# epm_control_2.net
KiCad netlist of a schematic drawn in Altium Designer
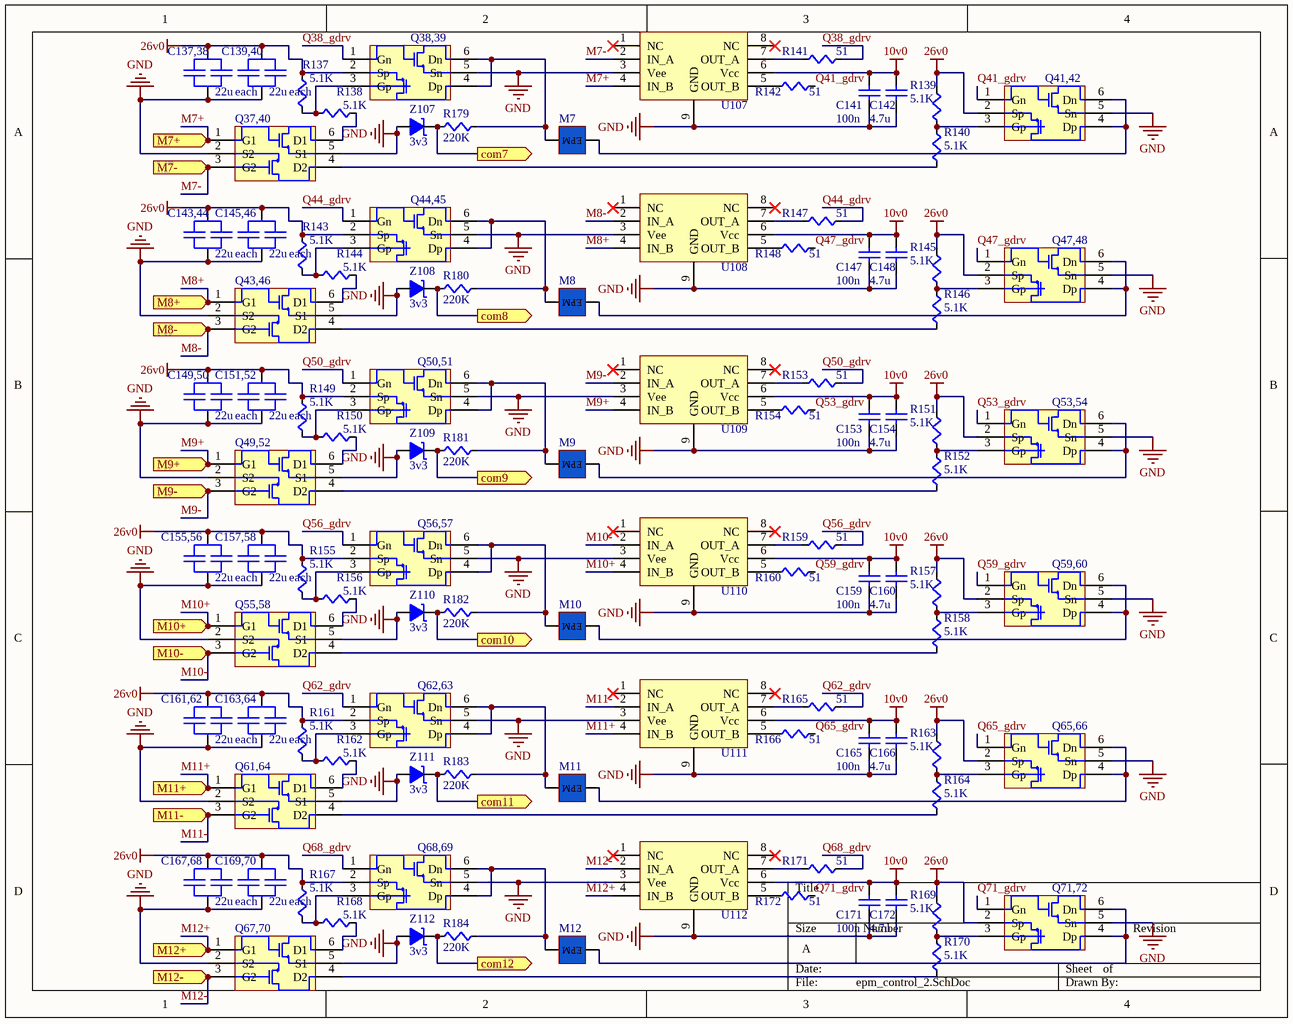
[diagram p0: epm_control_2.SchDoc]

(export (version "E")
  (design (tool "Eeschema 10.0.6"))
  (components
    (comp (ref "C137,38")
      (value "22u")
      (footprint "dicap_smd_1206")
      (fields (field (name "Comment") "Dicap"))
      (libsource (lib "Components") (part "Dicap"))
    )
    (comp (ref "C139,40")
      (value "22u")
      (footprint "dicap_smd_1206")
      (fields (field (name "Comment") "Dicap"))
      (libsource (lib "Components") (part "Dicap"))
    )
    (comp (ref "C141")
      (value "100n")
      (footprint "SMD0603_cap")
      (description "Ceramic Chip Capacitor")
      (fields (field (name "Comment") "Cap"))
      (libsource (lib "Components") (part "Capacitor Ceramic"))
    )
    (comp (ref "C142")
      (value "4.7u")
      (footprint "SMD0603_cap")
      (description "Ceramic Chip Capacitor")
      (fields (field (name "Comment") "Cap"))
      (libsource (lib "Components") (part "Capacitor Ceramic"))
    )
    (comp (ref "C143,44")
      (value "22u")
      (footprint "dicap_smd_1206")
      (fields (field (name "Comment") "Dicap"))
      (libsource (lib "Components") (part "Dicap"))
    )
    (comp (ref "C145,46")
      (value "22u")
      (footprint "dicap_smd_1206")
      (fields (field (name "Comment") "Dicap"))
      (libsource (lib "Components") (part "Dicap"))
    )
    (comp (ref "C147")
      (value "100n")
      (footprint "SMD0603_cap")
      (description "Ceramic Chip Capacitor")
      (fields (field (name "Comment") "Cap"))
      (libsource (lib "Components") (part "Capacitor Ceramic"))
    )
    (comp (ref "C148")
      (value "4.7u")
      (footprint "SMD0603_cap")
      (description "Ceramic Chip Capacitor")
      (fields (field (name "Comment") "Cap"))
      (libsource (lib "Components") (part "Capacitor Ceramic"))
    )
    (comp (ref "C149,50")
      (value "22u")
      (footprint "dicap_smd_1206")
      (fields (field (name "Comment") "Dicap"))
      (libsource (lib "Components") (part "Dicap"))
    )
    (comp (ref "C151,52")
      (value "22u")
      (footprint "dicap_smd_1206")
      (fields (field (name "Comment") "Dicap"))
      (libsource (lib "Components") (part "Dicap"))
    )
    (comp (ref "C153")
      (value "100n")
      (footprint "SMD0603_cap")
      (description "Ceramic Chip Capacitor")
      (fields (field (name "Comment") "Cap"))
      (libsource (lib "Components") (part "Capacitor Ceramic"))
    )
    (comp (ref "C154")
      (value "4.7u")
      (footprint "SMD0603_cap")
      (description "Ceramic Chip Capacitor")
      (fields (field (name "Comment") "Cap"))
      (libsource (lib "Components") (part "Capacitor Ceramic"))
    )
    (comp (ref "C155,56")
      (value "22u")
      (footprint "dicap_smd_1206")
      (fields (field (name "Comment") "Dicap"))
      (libsource (lib "Components") (part "Dicap"))
    )
    (comp (ref "C157,58")
      (value "22u")
      (footprint "dicap_smd_1206")
      (fields (field (name "Comment") "Dicap"))
      (libsource (lib "Components") (part "Dicap"))
    )
    (comp (ref "C159")
      (value "100n")
      (footprint "SMD0603_cap")
      (description "Ceramic Chip Capacitor")
      (fields (field (name "Comment") "Cap"))
      (libsource (lib "Components") (part "Capacitor Ceramic"))
    )
    (comp (ref "C160")
      (value "4.7u")
      (footprint "SMD0603_cap")
      (description "Ceramic Chip Capacitor")
      (fields (field (name "Comment") "Cap"))
      (libsource (lib "Components") (part "Capacitor Ceramic"))
    )
    (comp (ref "C161,62")
      (value "22u")
      (footprint "dicap_smd_1206")
      (fields (field (name "Comment") "Dicap"))
      (libsource (lib "Components") (part "Dicap"))
    )
    (comp (ref "C163,64")
      (value "22u")
      (footprint "dicap_smd_1206")
      (fields (field (name "Comment") "Dicap"))
      (libsource (lib "Components") (part "Dicap"))
    )
    (comp (ref "C165")
      (value "100n")
      (footprint "SMD0603_cap")
      (description "Ceramic Chip Capacitor")
      (fields (field (name "Comment") "Cap"))
      (libsource (lib "Components") (part "Capacitor Ceramic"))
    )
    (comp (ref "C166")
      (value "4.7u")
      (footprint "SMD0603_cap")
      (description "Ceramic Chip Capacitor")
      (fields (field (name "Comment") "Cap"))
      (libsource (lib "Components") (part "Capacitor Ceramic"))
    )
    (comp (ref "C167,68")
      (value "22u")
      (footprint "dicap_smd_1206")
      (fields (field (name "Comment") "Dicap"))
      (libsource (lib "Components") (part "Dicap"))
    )
    (comp (ref "C169,70")
      (value "22u")
      (footprint "dicap_smd_1206")
      (fields (field (name "Comment") "Dicap"))
      (libsource (lib "Components") (part "Dicap"))
    )
    (comp (ref "C171")
      (value "100n")
      (footprint "SMD0603_cap")
      (description "Ceramic Chip Capacitor")
      (fields (field (name "Comment") "Cap"))
      (libsource (lib "Components") (part "Capacitor Ceramic"))
    )
    (comp (ref "C172")
      (value "4.7u")
      (footprint "SMD0603_cap")
      (description "Ceramic Chip Capacitor")
      (fields (field (name "Comment") "Cap"))
      (libsource (lib "Components") (part "Capacitor Ceramic"))
    )
    (comp (ref "M7") (value "EPM") (footprint "40awg_epm") (libsource (lib "Components") (part "EPM")))
    (comp (ref "M8") (value "EPM") (footprint "40awg_epm") (libsource (lib "Components") (part "EPM")))
    (comp (ref "M9") (value "EPM") (footprint "40awg_epm") (libsource (lib "Components") (part "EPM")))
    (comp (ref "M10") (value "EPM") (footprint "40awg_epm") (libsource (lib "Components") (part "EPM")))
    (comp (ref "M11") (value "EPM") (footprint "40awg_epm") (libsource (lib "Components") (part "EPM")))
    (comp (ref "M12") (value "EPM") (footprint "40awg_epm") (libsource (lib "Components") (part "EPM")))
    (comp (ref "Q37,40")
      (value "SI3292")
      (footprint "sot23-6l")
      (libsource (lib "Components") (part "SI3292"))
    )
    (comp (ref "Q38,39")
      (value "DMG6602")
      (footprint "sot23-6l")
      (libsource (lib "Components") (part "DMG6602"))
    )
    (comp (ref "Q41,42")
      (value "DMG6602")
      (footprint "sot23-6l")
      (libsource (lib "Components") (part "DMG6602"))
    )
    (comp (ref "Q43,46")
      (value "SI3292")
      (footprint "sot23-6l")
      (libsource (lib "Components") (part "SI3292"))
    )
    (comp (ref "Q44,45")
      (value "DMG6602")
      (footprint "sot23-6l")
      (libsource (lib "Components") (part "DMG6602"))
    )
    (comp (ref "Q47,48")
      (value "DMG6602")
      (footprint "sot23-6l")
      (libsource (lib "Components") (part "DMG6602"))
    )
    (comp (ref "Q49,52")
      (value "SI3292")
      (footprint "sot23-6l")
      (libsource (lib "Components") (part "SI3292"))
    )
    (comp (ref "Q50,51")
      (value "DMG6602")
      (footprint "sot23-6l")
      (libsource (lib "Components") (part "DMG6602"))
    )
    (comp (ref "Q53,54")
      (value "DMG6602")
      (footprint "sot23-6l")
      (libsource (lib "Components") (part "DMG6602"))
    )
    (comp (ref "Q55,58")
      (value "SI3292")
      (footprint "sot23-6l")
      (libsource (lib "Components") (part "SI3292"))
    )
    (comp (ref "Q56,57")
      (value "DMG6602")
      (footprint "sot23-6l")
      (libsource (lib "Components") (part "DMG6602"))
    )
    (comp (ref "Q59,60")
      (value "DMG6602")
      (footprint "sot23-6l")
      (libsource (lib "Components") (part "DMG6602"))
    )
    (comp (ref "Q61,64")
      (value "SI3292")
      (footprint "sot23-6l")
      (libsource (lib "Components") (part "SI3292"))
    )
    (comp (ref "Q62,63")
      (value "DMG6602")
      (footprint "sot23-6l")
      (libsource (lib "Components") (part "DMG6602"))
    )
    (comp (ref "Q65,66")
      (value "DMG6602")
      (footprint "sot23-6l")
      (libsource (lib "Components") (part "DMG6602"))
    )
    (comp (ref "Q67,70")
      (value "SI3292")
      (footprint "sot23-6l")
      (libsource (lib "Components") (part "SI3292"))
    )
    (comp (ref "Q68,69")
      (value "DMG6602")
      (footprint "sot23-6l")
      (libsource (lib "Components") (part "DMG6602"))
    )
    (comp (ref "Q71,72")
      (value "DMG6602")
      (footprint "sot23-6l")
      (libsource (lib "Components") (part "DMG6602"))
    )
    (comp (ref "R137")
      (value "5.1K")
      (footprint "SMD0603")
      (description "Resistor")
      (fields (field (name "Comment") "Res"))
      (libsource (lib "Components") (part "Resistor"))
    )
    (comp (ref "R138")
      (value "5.1K")
      (footprint "SMD0603")
      (description "Resistor")
      (fields (field (name "Comment") "Res"))
      (libsource (lib "Components") (part "Resistor"))
    )
    (comp (ref "R139")
      (value "5.1K")
      (footprint "SMD0603")
      (description "Resistor")
      (fields (field (name "Comment") "Res"))
      (libsource (lib "Components") (part "Resistor"))
    )
    (comp (ref "R140")
      (value "5.1K")
      (footprint "SMD0603")
      (description "Resistor")
      (fields (field (name "Comment") "Res"))
      (libsource (lib "Components") (part "Resistor"))
    )
    (comp (ref "R141")
      (value "51")
      (footprint "SMD0603")
      (description "Resistor")
      (fields (field (name "Comment") "Res"))
      (libsource (lib "Components") (part "Resistor"))
    )
    (comp (ref "R142")
      (value "51")
      (footprint "SMD0603")
      (description "Resistor")
      (fields (field (name "Comment") "Res"))
      (libsource (lib "Components") (part "Resistor"))
    )
    (comp (ref "R143")
      (value "5.1K")
      (footprint "SMD0603")
      (description "Resistor")
      (fields (field (name "Comment") "Res"))
      (libsource (lib "Components") (part "Resistor"))
    )
    (comp (ref "R144")
      (value "5.1K")
      (footprint "SMD0603")
      (description "Resistor")
      (fields (field (name "Comment") "Res"))
      (libsource (lib "Components") (part "Resistor"))
    )
    (comp (ref "R145")
      (value "5.1K")
      (footprint "SMD0603")
      (description "Resistor")
      (fields (field (name "Comment") "Res"))
      (libsource (lib "Components") (part "Resistor"))
    )
    (comp (ref "R146")
      (value "5.1K")
      (footprint "SMD0603")
      (description "Resistor")
      (fields (field (name "Comment") "Res"))
      (libsource (lib "Components") (part "Resistor"))
    )
    (comp (ref "R147")
      (value "51")
      (footprint "SMD0603")
      (description "Resistor")
      (fields (field (name "Comment") "Res"))
      (libsource (lib "Components") (part "Resistor"))
    )
    (comp (ref "R148")
      (value "51")
      (footprint "SMD0603")
      (description "Resistor")
      (fields (field (name "Comment") "Res"))
      (libsource (lib "Components") (part "Resistor"))
    )
    (comp (ref "R149")
      (value "5.1K")
      (footprint "SMD0603")
      (description "Resistor")
      (fields (field (name "Comment") "Res"))
      (libsource (lib "Components") (part "Resistor"))
    )
    (comp (ref "R150")
      (value "5.1K")
      (footprint "SMD0603")
      (description "Resistor")
      (fields (field (name "Comment") "Res"))
      (libsource (lib "Components") (part "Resistor"))
    )
    (comp (ref "R151")
      (value "5.1K")
      (footprint "SMD0603")
      (description "Resistor")
      (fields (field (name "Comment") "Res"))
      (libsource (lib "Components") (part "Resistor"))
    )
    (comp (ref "R152")
      (value "5.1K")
      (footprint "SMD0603")
      (description "Resistor")
      (fields (field (name "Comment") "Res"))
      (libsource (lib "Components") (part "Resistor"))
    )
    (comp (ref "R153")
      (value "51")
      (footprint "SMD0603")
      (description "Resistor")
      (fields (field (name "Comment") "Res"))
      (libsource (lib "Components") (part "Resistor"))
    )
    (comp (ref "R154")
      (value "51")
      (footprint "SMD0603")
      (description "Resistor")
      (fields (field (name "Comment") "Res"))
      (libsource (lib "Components") (part "Resistor"))
    )
    (comp (ref "R155")
      (value "5.1K")
      (footprint "SMD0603")
      (description "Resistor")
      (fields (field (name "Comment") "Res"))
      (libsource (lib "Components") (part "Resistor"))
    )
    (comp (ref "R156")
      (value "5.1K")
      (footprint "SMD0603")
      (description "Resistor")
      (fields (field (name "Comment") "Res"))
      (libsource (lib "Components") (part "Resistor"))
    )
    (comp (ref "R157")
      (value "5.1K")
      (footprint "SMD0603")
      (description "Resistor")
      (fields (field (name "Comment") "Res"))
      (libsource (lib "Components") (part "Resistor"))
    )
    (comp (ref "R158")
      (value "5.1K")
      (footprint "SMD0603")
      (description "Resistor")
      (fields (field (name "Comment") "Res"))
      (libsource (lib "Components") (part "Resistor"))
    )
    (comp (ref "R159")
      (value "51")
      (footprint "SMD0603")
      (description "Resistor")
      (fields (field (name "Comment") "Res"))
      (libsource (lib "Components") (part "Resistor"))
    )
    (comp (ref "R160")
      (value "51")
      (footprint "SMD0603")
      (description "Resistor")
      (fields (field (name "Comment") "Res"))
      (libsource (lib "Components") (part "Resistor"))
    )
    (comp (ref "R161")
      (value "5.1K")
      (footprint "SMD0603")
      (description "Resistor")
      (fields (field (name "Comment") "Res"))
      (libsource (lib "Components") (part "Resistor"))
    )
    (comp (ref "R162")
      (value "5.1K")
      (footprint "SMD0603")
      (description "Resistor")
      (fields (field (name "Comment") "Res"))
      (libsource (lib "Components") (part "Resistor"))
    )
    (comp (ref "R163")
      (value "5.1K")
      (footprint "SMD0603")
      (description "Resistor")
      (fields (field (name "Comment") "Res"))
      (libsource (lib "Components") (part "Resistor"))
    )
    (comp (ref "R164")
      (value "5.1K")
      (footprint "SMD0603")
      (description "Resistor")
      (fields (field (name "Comment") "Res"))
      (libsource (lib "Components") (part "Resistor"))
    )
    (comp (ref "R165")
      (value "51")
      (footprint "SMD0603")
      (description "Resistor")
      (fields (field (name "Comment") "Res"))
      (libsource (lib "Components") (part "Resistor"))
    )
    (comp (ref "R166")
      (value "51")
      (footprint "SMD0603")
      (description "Resistor")
      (fields (field (name "Comment") "Res"))
      (libsource (lib "Components") (part "Resistor"))
    )
    (comp (ref "R167")
      (value "5.1K")
      (footprint "SMD0603")
      (description "Resistor")
      (fields (field (name "Comment") "Res"))
      (libsource (lib "Components") (part "Resistor"))
    )
    (comp (ref "R168")
      (value "5.1K")
      (footprint "SMD0603")
      (description "Resistor")
      (fields (field (name "Comment") "Res"))
      (libsource (lib "Components") (part "Resistor"))
    )
    (comp (ref "R169")
      (value "5.1K")
      (footprint "SMD0603")
      (description "Resistor")
      (fields (field (name "Comment") "Res"))
      (libsource (lib "Components") (part "Resistor"))
    )
    (comp (ref "R170")
      (value "5.1K")
      (footprint "SMD0603")
      (description "Resistor")
      (fields (field (name "Comment") "Res"))
      (libsource (lib "Components") (part "Resistor"))
    )
    (comp (ref "R171")
      (value "51")
      (footprint "SMD0603")
      (description "Resistor")
      (fields (field (name "Comment") "Res"))
      (libsource (lib "Components") (part "Resistor"))
    )
    (comp (ref "R172")
      (value "51")
      (footprint "SMD0603")
      (description "Resistor")
      (fields (field (name "Comment") "Res"))
      (libsource (lib "Components") (part "Resistor"))
    )
    (comp (ref "R179")
      (value "220K")
      (footprint "SMD0603")
      (description "Resistor")
      (fields (field (name "Comment") "Res"))
      (libsource (lib "Components") (part "Resistor"))
    )
    (comp (ref "R180")
      (value "220K")
      (footprint "SMD0603")
      (description "Resistor")
      (fields (field (name "Comment") "Res"))
      (libsource (lib "Components") (part "Resistor"))
    )
    (comp (ref "R181")
      (value "220K")
      (footprint "SMD0603")
      (description "Resistor")
      (fields (field (name "Comment") "Res"))
      (libsource (lib "Components") (part "Resistor"))
    )
    (comp (ref "R182")
      (value "220K")
      (footprint "SMD0603")
      (description "Resistor")
      (fields (field (name "Comment") "Res"))
      (libsource (lib "Components") (part "Resistor"))
    )
    (comp (ref "R183")
      (value "220K")
      (footprint "SMD0603")
      (description "Resistor")
      (fields (field (name "Comment") "Res"))
      (libsource (lib "Components") (part "Resistor"))
    )
    (comp (ref "R184")
      (value "220K")
      (footprint "SMD0603")
      (description "Resistor")
      (fields (field (name "Comment") "Res"))
      (libsource (lib "Components") (part "Resistor"))
    )
    (comp (ref "U107")
      (value "LM5111-1")
      (footprint "tssop-8")
      (libsource (lib "Components") (part "LM5111-1"))
    )
    (comp (ref "U108")
      (value "LM5111-1")
      (footprint "tssop-8")
      (libsource (lib "Components") (part "LM5111-1"))
    )
    (comp (ref "U109")
      (value "LM5111-1")
      (footprint "tssop-8")
      (libsource (lib "Components") (part "LM5111-1"))
    )
    (comp (ref "U110")
      (value "LM5111-1")
      (footprint "tssop-8")
      (libsource (lib "Components") (part "LM5111-1"))
    )
    (comp (ref "U111")
      (value "LM5111-1")
      (footprint "tssop-8")
      (libsource (lib "Components") (part "LM5111-1"))
    )
    (comp (ref "U112")
      (value "LM5111-1")
      (footprint "tssop-8")
      (libsource (lib "Components") (part "LM5111-1"))
    )
    (comp (ref "Z107")
      (value "3v3")
      (footprint "SOD-323F")
      (fields (field (name "Comment") "Zener"))
      (libsource (lib "Components") (part "Zener"))
    )
    (comp (ref "Z108")
      (value "3v3")
      (footprint "SOD-323F")
      (fields (field (name "Comment") "Zener"))
      (libsource (lib "Components") (part "Zener"))
    )
    (comp (ref "Z109")
      (value "3v3")
      (footprint "SOD-323F")
      (fields (field (name "Comment") "Zener"))
      (libsource (lib "Components") (part "Zener"))
    )
    (comp (ref "Z110")
      (value "3v3")
      (footprint "SOD-323F")
      (fields (field (name "Comment") "Zener"))
      (libsource (lib "Components") (part "Zener"))
    )
    (comp (ref "Z111")
      (value "3v3")
      (footprint "SOD-323F")
      (fields (field (name "Comment") "Zener"))
      (libsource (lib "Components") (part "Zener"))
    )
    (comp (ref "Z112")
      (value "3v3")
      (footprint "SOD-323F")
      (fields (field (name "Comment") "Zener"))
      (libsource (lib "Components") (part "Zener"))
    )
  )
  (nets
    (net (code "1") (name "/M7+") (class "Default")
      (node (ref "Q37,40") (pin "1") (pinfunction "G1_1") (pintype "passive"))
      (node (ref "U107") (pin "4") (pinfunction "IN_B_4") (pintype "passive"))
    )
    (net (code "2") (name "/M7-") (class "Default")
      (node (ref "Q37,40") (pin "3") (pinfunction "G2_3") (pintype "passive"))
      (node (ref "U107") (pin "2") (pinfunction "IN_A_2") (pintype "passive"))
    )
    (net (code "3") (name "/M8+") (class "Default")
      (node (ref "Q43,46") (pin "1") (pinfunction "G1_1") (pintype "passive"))
      (node (ref "U108") (pin "4") (pinfunction "IN_B_4") (pintype "passive"))
    )
    (net (code "4") (name "/M8-") (class "Default")
      (node (ref "Q43,46") (pin "3") (pinfunction "G2_3") (pintype "passive"))
      (node (ref "U108") (pin "2") (pinfunction "IN_A_2") (pintype "passive"))
    )
    (net (code "5") (name "/M9+") (class "Default")
      (node (ref "Q49,52") (pin "1") (pinfunction "G1_1") (pintype "passive"))
      (node (ref "U109") (pin "4") (pinfunction "IN_B_4") (pintype "passive"))
    )
    (net (code "6") (name "/M9-") (class "Default")
      (node (ref "Q49,52") (pin "3") (pinfunction "G2_3") (pintype "passive"))
      (node (ref "U109") (pin "2") (pinfunction "IN_A_2") (pintype "passive"))
    )
    (net (code "7") (name "/M10+") (class "Default")
      (node (ref "Q55,58") (pin "1") (pinfunction "G1_1") (pintype "passive"))
      (node (ref "U110") (pin "4") (pinfunction "IN_B_4") (pintype "passive"))
    )
    (net (code "8") (name "/M10-") (class "Default")
      (node (ref "Q55,58") (pin "3") (pinfunction "G2_3") (pintype "passive"))
      (node (ref "U110") (pin "2") (pinfunction "IN_A_2") (pintype "passive"))
    )
    (net (code "9") (name "/M11+") (class "Default")
      (node (ref "Q61,64") (pin "1") (pinfunction "G1_1") (pintype "passive"))
      (node (ref "U111") (pin "4") (pinfunction "IN_B_4") (pintype "passive"))
    )
    (net (code "10") (name "/M11-") (class "Default")
      (node (ref "Q61,64") (pin "3") (pinfunction "G2_3") (pintype "passive"))
      (node (ref "U111") (pin "2") (pinfunction "IN_A_2") (pintype "passive"))
    )
    (net (code "11") (name "/M12+") (class "Default")
      (node (ref "Q67,70") (pin "1") (pinfunction "G1_1") (pintype "passive"))
      (node (ref "U112") (pin "4") (pinfunction "IN_B_4") (pintype "passive"))
    )
    (net (code "12") (name "/M12-") (class "Default")
      (node (ref "Q67,70") (pin "3") (pinfunction "G2_3") (pintype "passive"))
      (node (ref "U112") (pin "2") (pinfunction "IN_A_2") (pintype "passive"))
    )
    (net (code "13") (name "/Q38_gdrv") (class "Default")
      (node (ref "Q38,39") (pin "1") (pinfunction "Gn_1") (pintype "passive"))
      (node (ref "R141") (pin "1") (pinfunction "1_1") (pintype "passive"))
    )
    (net (code "14") (name "/Q41_gdrv") (class "Default")
      (node (ref "Q41,42") (pin "1") (pinfunction "Gn_1") (pintype "passive"))
      (node (ref "R142") (pin "1") (pinfunction "1_1") (pintype "passive"))
    )
    (net (code "15") (name "/Q44_gdrv") (class "Default")
      (node (ref "Q44,45") (pin "1") (pinfunction "Gn_1") (pintype "passive"))
      (node (ref "R147") (pin "1") (pinfunction "1_1") (pintype "passive"))
    )
    (net (code "16") (name "/Q47_gdrv") (class "Default")
      (node (ref "Q47,48") (pin "1") (pinfunction "Gn_1") (pintype "passive"))
      (node (ref "R148") (pin "1") (pinfunction "1_1") (pintype "passive"))
    )
    (net (code "17") (name "/Q50_gdrv") (class "Default")
      (node (ref "Q50,51") (pin "1") (pinfunction "Gn_1") (pintype "passive"))
      (node (ref "R153") (pin "1") (pinfunction "1_1") (pintype "passive"))
    )
    (net (code "18") (name "/Q53_gdrv") (class "Default")
      (node (ref "Q53,54") (pin "1") (pinfunction "Gn_1") (pintype "passive"))
      (node (ref "R154") (pin "1") (pinfunction "1_1") (pintype "passive"))
    )
    (net (code "19") (name "/Q56_gdrv") (class "Default")
      (node (ref "Q56,57") (pin "1") (pinfunction "Gn_1") (pintype "passive"))
      (node (ref "R159") (pin "1") (pinfunction "1_1") (pintype "passive"))
    )
    (net (code "20") (name "/Q59_gdrv") (class "Default")
      (node (ref "Q59,60") (pin "1") (pinfunction "Gn_1") (pintype "passive"))
      (node (ref "R160") (pin "1") (pinfunction "1_1") (pintype "passive"))
    )
    (net (code "21") (name "/Q62_gdrv") (class "Default")
      (node (ref "Q62,63") (pin "1") (pinfunction "Gn_1") (pintype "passive"))
      (node (ref "R165") (pin "1") (pinfunction "1_1") (pintype "passive"))
    )
    (net (code "22") (name "/Q65_gdrv") (class "Default")
      (node (ref "Q65,66") (pin "1") (pinfunction "Gn_1") (pintype "passive"))
      (node (ref "R166") (pin "1") (pinfunction "1_1") (pintype "passive"))
    )
    (net (code "23") (name "/Q68_gdrv") (class "Default")
      (node (ref "Q68,69") (pin "1") (pinfunction "Gn_1") (pintype "passive"))
      (node (ref "R171") (pin "1") (pinfunction "1_1") (pintype "passive"))
    )
    (net (code "24") (name "/Q71_gdrv") (class "Default")
      (node (ref "Q71,72") (pin "1") (pinfunction "Gn_1") (pintype "passive"))
      (node (ref "R172") (pin "1") (pinfunction "1_1") (pintype "passive"))
    )
    (net (code "25") (name "/com7") (class "Default")
      (node (ref "R179") (pin "1") (pinfunction "1_1") (pintype "passive"))
      (node (ref "Z107") (pin "K") (pinfunction "2_K") (pintype "passive"))
    )
    (net (code "26") (name "/com8") (class "Default")
      (node (ref "R180") (pin "1") (pinfunction "1_1") (pintype "passive"))
      (node (ref "Z108") (pin "K") (pinfunction "2_K") (pintype "passive"))
    )
    (net (code "27") (name "/com9") (class "Default")
      (node (ref "R181") (pin "1") (pinfunction "1_1") (pintype "passive"))
      (node (ref "Z109") (pin "K") (pinfunction "2_K") (pintype "passive"))
    )
    (net (code "28") (name "/com10") (class "Default")
      (node (ref "R182") (pin "1") (pinfunction "1_1") (pintype "passive"))
      (node (ref "Z110") (pin "K") (pinfunction "2_K") (pintype "passive"))
    )
    (net (code "29") (name "/com11") (class "Default")
      (node (ref "R183") (pin "1") (pinfunction "1_1") (pintype "passive"))
      (node (ref "Z111") (pin "K") (pinfunction "2_K") (pintype "passive"))
    )
    (net (code "30") (name "/com12") (class "Default")
      (node (ref "R184") (pin "1") (pinfunction "1_1") (pintype "passive"))
      (node (ref "Z112") (pin "K") (pinfunction "2_K") (pintype "passive"))
    )
    (net (code "31") (name "10v0") (class "Default")
      (node (ref "C141") (pin "2") (pinfunction "2_2") (pintype "passive"))
      (node (ref "C142") (pin "2") (pinfunction "2_2") (pintype "passive"))
      (node (ref "C147") (pin "2") (pinfunction "2_2") (pintype "passive"))
      (node (ref "C148") (pin "2") (pinfunction "2_2") (pintype "passive"))
      (node (ref "C153") (pin "2") (pinfunction "2_2") (pintype "passive"))
      (node (ref "C154") (pin "2") (pinfunction "2_2") (pintype "passive"))
      (node (ref "C159") (pin "2") (pinfunction "2_2") (pintype "passive"))
      (node (ref "C160") (pin "2") (pinfunction "2_2") (pintype "passive"))
      (node (ref "C165") (pin "2") (pinfunction "2_2") (pintype "passive"))
      (node (ref "C166") (pin "2") (pinfunction "2_2") (pintype "passive"))
      (node (ref "C171") (pin "2") (pinfunction "2_2") (pintype "passive"))
      (node (ref "C172") (pin "2") (pinfunction "2_2") (pintype "passive"))
      (node (ref "U107") (pin "6") (pinfunction "Vcc_6") (pintype "passive"))
      (node (ref "U108") (pin "6") (pinfunction "Vcc_6") (pintype "passive"))
      (node (ref "U109") (pin "6") (pinfunction "Vcc_6") (pintype "passive"))
      (node (ref "U110") (pin "6") (pinfunction "Vcc_6") (pintype "passive"))
      (node (ref "U111") (pin "6") (pinfunction "Vcc_6") (pintype "passive"))
      (node (ref "U112") (pin "6") (pinfunction "Vcc_6") (pintype "passive"))
    )
    (net (code "32") (name "26v0") (class "Default")
      (node (ref "C137,38") (pin "2") (pinfunction "2_2") (pintype "passive"))
      (node (ref "C139,40") (pin "2") (pinfunction "2_2") (pintype "passive"))
      (node (ref "C143,44") (pin "2") (pinfunction "2_2") (pintype "passive"))
      (node (ref "C145,46") (pin "2") (pinfunction "2_2") (pintype "passive"))
      (node (ref "C149,50") (pin "2") (pinfunction "2_2") (pintype "passive"))
      (node (ref "C151,52") (pin "2") (pinfunction "2_2") (pintype "passive"))
      (node (ref "C155,56") (pin "2") (pinfunction "2_2") (pintype "passive"))
      (node (ref "C157,58") (pin "2") (pinfunction "2_2") (pintype "passive"))
      (node (ref "C161,62") (pin "2") (pinfunction "2_2") (pintype "passive"))
      (node (ref "C163,64") (pin "2") (pinfunction "2_2") (pintype "passive"))
      (node (ref "C167,68") (pin "2") (pinfunction "2_2") (pintype "passive"))
      (node (ref "C169,70") (pin "2") (pinfunction "2_2") (pintype "passive"))
      (node (ref "Q38,39") (pin "2") (pinfunction "Sp_2") (pintype "passive"))
      (node (ref "Q41,42") (pin "2") (pinfunction "Sp_2") (pintype "passive"))
      (node (ref "Q44,45") (pin "2") (pinfunction "Sp_2") (pintype "passive"))
      (node (ref "Q47,48") (pin "2") (pinfunction "Sp_2") (pintype "passive"))
      (node (ref "Q50,51") (pin "2") (pinfunction "Sp_2") (pintype "passive"))
      (node (ref "Q53,54") (pin "2") (pinfunction "Sp_2") (pintype "passive"))
      (node (ref "Q56,57") (pin "2") (pinfunction "Sp_2") (pintype "passive"))
      (node (ref "Q59,60") (pin "2") (pinfunction "Sp_2") (pintype "passive"))
      (node (ref "Q62,63") (pin "2") (pinfunction "Sp_2") (pintype "passive"))
      (node (ref "Q65,66") (pin "2") (pinfunction "Sp_2") (pintype "passive"))
      (node (ref "Q68,69") (pin "2") (pinfunction "Sp_2") (pintype "passive"))
      (node (ref "Q71,72") (pin "2") (pinfunction "Sp_2") (pintype "passive"))
      (node (ref "R137") (pin "2") (pinfunction "2_2") (pintype "passive"))
      (node (ref "R139") (pin "2") (pinfunction "2_2") (pintype "passive"))
      (node (ref "R143") (pin "2") (pinfunction "2_2") (pintype "passive"))
      (node (ref "R145") (pin "2") (pinfunction "2_2") (pintype "passive"))
      (node (ref "R149") (pin "2") (pinfunction "2_2") (pintype "passive"))
      (node (ref "R151") (pin "2") (pinfunction "2_2") (pintype "passive"))
      (node (ref "R155") (pin "2") (pinfunction "2_2") (pintype "passive"))
      (node (ref "R157") (pin "2") (pinfunction "2_2") (pintype "passive"))
      (node (ref "R161") (pin "2") (pinfunction "2_2") (pintype "passive"))
      (node (ref "R163") (pin "2") (pinfunction "2_2") (pintype "passive"))
      (node (ref "R167") (pin "2") (pinfunction "2_2") (pintype "passive"))
      (node (ref "R169") (pin "2") (pinfunction "2_2") (pintype "passive"))
    )
    (net (code "33") (name "GND") (class "Default")
      (node (ref "C137,38") (pin "1") (pinfunction "1_1") (pintype "passive"))
      (node (ref "C139,40") (pin "1") (pinfunction "1_1") (pintype "passive"))
      (node (ref "C141") (pin "1") (pinfunction "1_1") (pintype "passive"))
      (node (ref "C142") (pin "1") (pinfunction "1_1") (pintype "passive"))
      (node (ref "C143,44") (pin "1") (pinfunction "1_1") (pintype "passive"))
      (node (ref "C145,46") (pin "1") (pinfunction "1_1") (pintype "passive"))
      (node (ref "C147") (pin "1") (pinfunction "1_1") (pintype "passive"))
      (node (ref "C148") (pin "1") (pinfunction "1_1") (pintype "passive"))
      (node (ref "C149,50") (pin "1") (pinfunction "1_1") (pintype "passive"))
      (node (ref "C151,52") (pin "1") (pinfunction "1_1") (pintype "passive"))
      (node (ref "C153") (pin "1") (pinfunction "1_1") (pintype "passive"))
      (node (ref "C154") (pin "1") (pinfunction "1_1") (pintype "passive"))
      (node (ref "C155,56") (pin "1") (pinfunction "1_1") (pintype "passive"))
      (node (ref "C157,58") (pin "1") (pinfunction "1_1") (pintype "passive"))
      (node (ref "C159") (pin "1") (pinfunction "1_1") (pintype "passive"))
      (node (ref "C160") (pin "1") (pinfunction "1_1") (pintype "passive"))
      (node (ref "C161,62") (pin "1") (pinfunction "1_1") (pintype "passive"))
      (node (ref "C163,64") (pin "1") (pinfunction "1_1") (pintype "passive"))
      (node (ref "C165") (pin "1") (pinfunction "1_1") (pintype "passive"))
      (node (ref "C166") (pin "1") (pinfunction "1_1") (pintype "passive"))
      (node (ref "C167,68") (pin "1") (pinfunction "1_1") (pintype "passive"))
      (node (ref "C169,70") (pin "1") (pinfunction "1_1") (pintype "passive"))
      (node (ref "C171") (pin "1") (pinfunction "1_1") (pintype "passive"))
      (node (ref "C172") (pin "1") (pinfunction "1_1") (pintype "passive"))
      (node (ref "Q37,40") (pin "2") (pinfunction "S2_2") (pintype "passive"))
      (node (ref "Q37,40") (pin "5") (pinfunction "S1_5") (pintype "passive"))
      (node (ref "Q38,39") (pin "5") (pinfunction "Sn_5") (pintype "passive"))
      (node (ref "Q41,42") (pin "5") (pinfunction "Sn_5") (pintype "passive"))
      (node (ref "Q43,46") (pin "2") (pinfunction "S2_2") (pintype "passive"))
      (node (ref "Q43,46") (pin "5") (pinfunction "S1_5") (pintype "passive"))
      (node (ref "Q44,45") (pin "5") (pinfunction "Sn_5") (pintype "passive"))
      (node (ref "Q47,48") (pin "5") (pinfunction "Sn_5") (pintype "passive"))
      (node (ref "Q49,52") (pin "2") (pinfunction "S2_2") (pintype "passive"))
      (node (ref "Q49,52") (pin "5") (pinfunction "S1_5") (pintype "passive"))
      (node (ref "Q50,51") (pin "5") (pinfunction "Sn_5") (pintype "passive"))
      (node (ref "Q53,54") (pin "5") (pinfunction "Sn_5") (pintype "passive"))
      (node (ref "Q55,58") (pin "2") (pinfunction "S2_2") (pintype "passive"))
      (node (ref "Q55,58") (pin "5") (pinfunction "S1_5") (pintype "passive"))
      (node (ref "Q56,57") (pin "5") (pinfunction "Sn_5") (pintype "passive"))
      (node (ref "Q59,60") (pin "5") (pinfunction "Sn_5") (pintype "passive"))
      (node (ref "Q61,64") (pin "2") (pinfunction "S2_2") (pintype "passive"))
      (node (ref "Q61,64") (pin "5") (pinfunction "S1_5") (pintype "passive"))
      (node (ref "Q62,63") (pin "5") (pinfunction "Sn_5") (pintype "passive"))
      (node (ref "Q65,66") (pin "5") (pinfunction "Sn_5") (pintype "passive"))
      (node (ref "Q67,70") (pin "2") (pinfunction "S2_2") (pintype "passive"))
      (node (ref "Q67,70") (pin "5") (pinfunction "S1_5") (pintype "passive"))
      (node (ref "Q68,69") (pin "5") (pinfunction "Sn_5") (pintype "passive"))
      (node (ref "Q71,72") (pin "5") (pinfunction "Sn_5") (pintype "passive"))
      (node (ref "U107") (pin "3") (pinfunction "Vee_3") (pintype "passive"))
      (node (ref "U107") (pin "9") (pinfunction "GND_9") (pintype "passive"))
      (node (ref "U108") (pin "3") (pinfunction "Vee_3") (pintype "passive"))
      (node (ref "U108") (pin "9") (pinfunction "GND_9") (pintype "passive"))
      (node (ref "U109") (pin "3") (pinfunction "Vee_3") (pintype "passive"))
      (node (ref "U109") (pin "9") (pinfunction "GND_9") (pintype "passive"))
      (node (ref "U110") (pin "3") (pinfunction "Vee_3") (pintype "passive"))
      (node (ref "U110") (pin "9") (pinfunction "GND_9") (pintype "passive"))
      (node (ref "U111") (pin "3") (pinfunction "Vee_3") (pintype "passive"))
      (node (ref "U111") (pin "9") (pinfunction "GND_9") (pintype "passive"))
      (node (ref "U112") (pin "3") (pinfunction "Vee_3") (pintype "passive"))
      (node (ref "U112") (pin "9") (pinfunction "GND_9") (pintype "passive"))
      (node (ref "Z107") (pin "A") (pintype "passive"))
      (node (ref "Z108") (pin "A") (pintype "passive"))
      (node (ref "Z109") (pin "A") (pintype "passive"))
      (node (ref "Z110") (pin "A") (pintype "passive"))
      (node (ref "Z111") (pin "A") (pintype "passive"))
      (node (ref "Z112") (pin "A") (pintype "passive"))
    )
    (net (code "34") (name "Net-(Q37,40-D1)") (class "Default")
      (node (ref "Q37,40") (pin "6") (pinfunction "D1_6") (pintype "passive"))
      (node (ref "R138") (pin "1") (pinfunction "1_1") (pintype "passive"))
    )
    (net (code "35") (name "Net-(Q37,40-D2)") (class "Default")
      (node (ref "Q37,40") (pin "4") (pinfunction "D2_4") (pintype "passive"))
      (node (ref "R140") (pin "1") (pinfunction "1_1") (pintype "passive"))
    )
    (net (code "36") (name "Net-(Q38,39-Dn)") (class "Default")
      (node (ref "M7") (pin "2") (pinfunction "2_2") (pintype "passive"))
      (node (ref "Q38,39") (pin "4") (pinfunction "Dp_4") (pintype "passive"))
      (node (ref "Q38,39") (pin "6") (pinfunction "Dn_6") (pintype "passive"))
      (node (ref "R179") (pin "2") (pinfunction "2_2") (pintype "passive"))
    )
    (net (code "37") (name "Net-(Q38,39-Gp)") (class "Default")
      (node (ref "Q38,39") (pin "3") (pinfunction "Gp_3") (pintype "passive"))
      (node (ref "R137") (pin "1") (pinfunction "1_1") (pintype "passive"))
      (node (ref "R138") (pin "2") (pinfunction "2_2") (pintype "passive"))
    )
    (net (code "38") (name "Net-(Q41,42-Dn)") (class "Default")
      (node (ref "M7") (pin "1") (pinfunction "1_1") (pintype "passive"))
      (node (ref "Q41,42") (pin "4") (pinfunction "Dp_4") (pintype "passive"))
      (node (ref "Q41,42") (pin "6") (pinfunction "Dn_6") (pintype "passive"))
    )
    (net (code "39") (name "Net-(Q41,42-Gp)") (class "Default")
      (node (ref "Q41,42") (pin "3") (pinfunction "Gp_3") (pintype "passive"))
      (node (ref "R139") (pin "1") (pinfunction "1_1") (pintype "passive"))
      (node (ref "R140") (pin "2") (pinfunction "2_2") (pintype "passive"))
    )
    (net (code "40") (name "Net-(Q43,46-D1)") (class "Default")
      (node (ref "Q43,46") (pin "6") (pinfunction "D1_6") (pintype "passive"))
      (node (ref "R144") (pin "1") (pinfunction "1_1") (pintype "passive"))
    )
    (net (code "41") (name "Net-(Q43,46-D2)") (class "Default")
      (node (ref "Q43,46") (pin "4") (pinfunction "D2_4") (pintype "passive"))
      (node (ref "R146") (pin "1") (pinfunction "1_1") (pintype "passive"))
    )
    (net (code "42") (name "Net-(Q44,45-Dn)") (class "Default")
      (node (ref "M8") (pin "2") (pinfunction "2_2") (pintype "passive"))
      (node (ref "Q44,45") (pin "4") (pinfunction "Dp_4") (pintype "passive"))
      (node (ref "Q44,45") (pin "6") (pinfunction "Dn_6") (pintype "passive"))
      (node (ref "R180") (pin "2") (pinfunction "2_2") (pintype "passive"))
    )
    (net (code "43") (name "Net-(Q44,45-Gp)") (class "Default")
      (node (ref "Q44,45") (pin "3") (pinfunction "Gp_3") (pintype "passive"))
      (node (ref "R143") (pin "1") (pinfunction "1_1") (pintype "passive"))
      (node (ref "R144") (pin "2") (pinfunction "2_2") (pintype "passive"))
    )
    (net (code "44") (name "Net-(Q47,48-Dn)") (class "Default")
      (node (ref "M8") (pin "1") (pinfunction "1_1") (pintype "passive"))
      (node (ref "Q47,48") (pin "4") (pinfunction "Dp_4") (pintype "passive"))
      (node (ref "Q47,48") (pin "6") (pinfunction "Dn_6") (pintype "passive"))
    )
    (net (code "45") (name "Net-(Q47,48-Gp)") (class "Default")
      (node (ref "Q47,48") (pin "3") (pinfunction "Gp_3") (pintype "passive"))
      (node (ref "R145") (pin "1") (pinfunction "1_1") (pintype "passive"))
      (node (ref "R146") (pin "2") (pinfunction "2_2") (pintype "passive"))
    )
    (net (code "46") (name "Net-(Q49,52-D1)") (class "Default")
      (node (ref "Q49,52") (pin "6") (pinfunction "D1_6") (pintype "passive"))
      (node (ref "R150") (pin "1") (pinfunction "1_1") (pintype "passive"))
    )
    (net (code "47") (name "Net-(Q49,52-D2)") (class "Default")
      (node (ref "Q49,52") (pin "4") (pinfunction "D2_4") (pintype "passive"))
      (node (ref "R152") (pin "1") (pinfunction "1_1") (pintype "passive"))
    )
    (net (code "48") (name "Net-(Q50,51-Dn)") (class "Default")
      (node (ref "M9") (pin "2") (pinfunction "2_2") (pintype "passive"))
      (node (ref "Q50,51") (pin "4") (pinfunction "Dp_4") (pintype "passive"))
      (node (ref "Q50,51") (pin "6") (pinfunction "Dn_6") (pintype "passive"))
      (node (ref "R181") (pin "2") (pinfunction "2_2") (pintype "passive"))
    )
    (net (code "49") (name "Net-(Q50,51-Gp)") (class "Default")
      (node (ref "Q50,51") (pin "3") (pinfunction "Gp_3") (pintype "passive"))
      (node (ref "R149") (pin "1") (pinfunction "1_1") (pintype "passive"))
      (node (ref "R150") (pin "2") (pinfunction "2_2") (pintype "passive"))
    )
    (net (code "50") (name "Net-(Q53,54-Dn)") (class "Default")
      (node (ref "M9") (pin "1") (pinfunction "1_1") (pintype "passive"))
      (node (ref "Q53,54") (pin "4") (pinfunction "Dp_4") (pintype "passive"))
      (node (ref "Q53,54") (pin "6") (pinfunction "Dn_6") (pintype "passive"))
    )
    (net (code "51") (name "Net-(Q53,54-Gp)") (class "Default")
      (node (ref "Q53,54") (pin "3") (pinfunction "Gp_3") (pintype "passive"))
      (node (ref "R151") (pin "1") (pinfunction "1_1") (pintype "passive"))
      (node (ref "R152") (pin "2") (pinfunction "2_2") (pintype "passive"))
    )
    (net (code "52") (name "Net-(Q55,58-D1)") (class "Default")
      (node (ref "Q55,58") (pin "6") (pinfunction "D1_6") (pintype "passive"))
      (node (ref "R156") (pin "1") (pinfunction "1_1") (pintype "passive"))
    )
    (net (code "53") (name "Net-(Q55,58-D2)") (class "Default")
      (node (ref "Q55,58") (pin "4") (pinfunction "D2_4") (pintype "passive"))
      (node (ref "R158") (pin "1") (pinfunction "1_1") (pintype "passive"))
    )
    (net (code "54") (name "Net-(Q56,57-Dn)") (class "Default")
      (node (ref "M10") (pin "2") (pinfunction "2_2") (pintype "passive"))
      (node (ref "Q56,57") (pin "4") (pinfunction "Dp_4") (pintype "passive"))
      (node (ref "Q56,57") (pin "6") (pinfunction "Dn_6") (pintype "passive"))
      (node (ref "R182") (pin "2") (pinfunction "2_2") (pintype "passive"))
    )
    (net (code "55") (name "Net-(Q56,57-Gp)") (class "Default")
      (node (ref "Q56,57") (pin "3") (pinfunction "Gp_3") (pintype "passive"))
      (node (ref "R155") (pin "1") (pinfunction "1_1") (pintype "passive"))
      (node (ref "R156") (pin "2") (pinfunction "2_2") (pintype "passive"))
    )
    (net (code "56") (name "Net-(Q59,60-Dn)") (class "Default")
      (node (ref "M10") (pin "1") (pinfunction "1_1") (pintype "passive"))
      (node (ref "Q59,60") (pin "4") (pinfunction "Dp_4") (pintype "passive"))
      (node (ref "Q59,60") (pin "6") (pinfunction "Dn_6") (pintype "passive"))
    )
    (net (code "57") (name "Net-(Q59,60-Gp)") (class "Default")
      (node (ref "Q59,60") (pin "3") (pinfunction "Gp_3") (pintype "passive"))
      (node (ref "R157") (pin "1") (pinfunction "1_1") (pintype "passive"))
      (node (ref "R158") (pin "2") (pinfunction "2_2") (pintype "passive"))
    )
    (net (code "58") (name "Net-(Q61,64-D1)") (class "Default")
      (node (ref "Q61,64") (pin "6") (pinfunction "D1_6") (pintype "passive"))
      (node (ref "R162") (pin "1") (pinfunction "1_1") (pintype "passive"))
    )
    (net (code "59") (name "Net-(Q61,64-D2)") (class "Default")
      (node (ref "Q61,64") (pin "4") (pinfunction "D2_4") (pintype "passive"))
      (node (ref "R164") (pin "1") (pinfunction "1_1") (pintype "passive"))
    )
    (net (code "60") (name "Net-(Q62,63-Dn)") (class "Default")
      (node (ref "M11") (pin "2") (pinfunction "2_2") (pintype "passive"))
      (node (ref "Q62,63") (pin "4") (pinfunction "Dp_4") (pintype "passive"))
      (node (ref "Q62,63") (pin "6") (pinfunction "Dn_6") (pintype "passive"))
      (node (ref "R183") (pin "2") (pinfunction "2_2") (pintype "passive"))
    )
    (net (code "61") (name "Net-(Q62,63-Gp)") (class "Default")
      (node (ref "Q62,63") (pin "3") (pinfunction "Gp_3") (pintype "passive"))
      (node (ref "R161") (pin "1") (pinfunction "1_1") (pintype "passive"))
      (node (ref "R162") (pin "2") (pinfunction "2_2") (pintype "passive"))
    )
    (net (code "62") (name "Net-(Q65,66-Dn)") (class "Default")
      (node (ref "M11") (pin "1") (pinfunction "1_1") (pintype "passive"))
      (node (ref "Q65,66") (pin "4") (pinfunction "Dp_4") (pintype "passive"))
      (node (ref "Q65,66") (pin "6") (pinfunction "Dn_6") (pintype "passive"))
    )
    (net (code "63") (name "Net-(Q65,66-Gp)") (class "Default")
      (node (ref "Q65,66") (pin "3") (pinfunction "Gp_3") (pintype "passive"))
      (node (ref "R163") (pin "1") (pinfunction "1_1") (pintype "passive"))
      (node (ref "R164") (pin "2") (pinfunction "2_2") (pintype "passive"))
    )
    (net (code "64") (name "Net-(Q67,70-D1)") (class "Default")
      (node (ref "Q67,70") (pin "6") (pinfunction "D1_6") (pintype "passive"))
      (node (ref "R168") (pin "1") (pinfunction "1_1") (pintype "passive"))
    )
    (net (code "65") (name "Net-(Q67,70-D2)") (class "Default")
      (node (ref "Q67,70") (pin "4") (pinfunction "D2_4") (pintype "passive"))
      (node (ref "R170") (pin "1") (pinfunction "1_1") (pintype "passive"))
    )
    (net (code "66") (name "Net-(Q68,69-Dn)") (class "Default")
      (node (ref "M12") (pin "2") (pinfunction "2_2") (pintype "passive"))
      (node (ref "Q68,69") (pin "4") (pinfunction "Dp_4") (pintype "passive"))
      (node (ref "Q68,69") (pin "6") (pinfunction "Dn_6") (pintype "passive"))
      (node (ref "R184") (pin "2") (pinfunction "2_2") (pintype "passive"))
    )
    (net (code "67") (name "Net-(Q68,69-Gp)") (class "Default")
      (node (ref "Q68,69") (pin "3") (pinfunction "Gp_3") (pintype "passive"))
      (node (ref "R167") (pin "1") (pinfunction "1_1") (pintype "passive"))
      (node (ref "R168") (pin "2") (pinfunction "2_2") (pintype "passive"))
    )
    (net (code "68") (name "Net-(Q71,72-Dn)") (class "Default")
      (node (ref "M12") (pin "1") (pinfunction "1_1") (pintype "passive"))
      (node (ref "Q71,72") (pin "4") (pinfunction "Dp_4") (pintype "passive"))
      (node (ref "Q71,72") (pin "6") (pinfunction "Dn_6") (pintype "passive"))
    )
    (net (code "69") (name "Net-(Q71,72-Gp)") (class "Default")
      (node (ref "Q71,72") (pin "3") (pinfunction "Gp_3") (pintype "passive"))
      (node (ref "R169") (pin "1") (pinfunction "1_1") (pintype "passive"))
      (node (ref "R170") (pin "2") (pinfunction "2_2") (pintype "passive"))
    )
    (net (code "70") (name "Net-(U107-OUT_A)") (class "Default")
      (node (ref "R141") (pin "2") (pinfunction "2_2") (pintype "passive"))
      (node (ref "U107") (pin "7") (pinfunction "OUT_A_7") (pintype "passive"))
    )
    (net (code "71") (name "Net-(U107-OUT_B)") (class "Default")
      (node (ref "R142") (pin "2") (pinfunction "2_2") (pintype "passive"))
      (node (ref "U107") (pin "5") (pinfunction "OUT_B_5") (pintype "passive"))
    )
    (net (code "72") (name "Net-(U108-OUT_A)") (class "Default")
      (node (ref "R147") (pin "2") (pinfunction "2_2") (pintype "passive"))
      (node (ref "U108") (pin "7") (pinfunction "OUT_A_7") (pintype "passive"))
    )
    (net (code "73") (name "Net-(U108-OUT_B)") (class "Default")
      (node (ref "R148") (pin "2") (pinfunction "2_2") (pintype "passive"))
      (node (ref "U108") (pin "5") (pinfunction "OUT_B_5") (pintype "passive"))
    )
    (net (code "74") (name "Net-(U109-OUT_A)") (class "Default")
      (node (ref "R153") (pin "2") (pinfunction "2_2") (pintype "passive"))
      (node (ref "U109") (pin "7") (pinfunction "OUT_A_7") (pintype "passive"))
    )
    (net (code "75") (name "Net-(U109-OUT_B)") (class "Default")
      (node (ref "R154") (pin "2") (pinfunction "2_2") (pintype "passive"))
      (node (ref "U109") (pin "5") (pinfunction "OUT_B_5") (pintype "passive"))
    )
    (net (code "76") (name "Net-(U110-OUT_A)") (class "Default")
      (node (ref "R159") (pin "2") (pinfunction "2_2") (pintype "passive"))
      (node (ref "U110") (pin "7") (pinfunction "OUT_A_7") (pintype "passive"))
    )
    (net (code "77") (name "Net-(U110-OUT_B)") (class "Default")
      (node (ref "R160") (pin "2") (pinfunction "2_2") (pintype "passive"))
      (node (ref "U110") (pin "5") (pinfunction "OUT_B_5") (pintype "passive"))
    )
    (net (code "78") (name "Net-(U111-OUT_A)") (class "Default")
      (node (ref "R165") (pin "2") (pinfunction "2_2") (pintype "passive"))
      (node (ref "U111") (pin "7") (pinfunction "OUT_A_7") (pintype "passive"))
    )
    (net (code "79") (name "Net-(U111-OUT_B)") (class "Default")
      (node (ref "R166") (pin "2") (pinfunction "2_2") (pintype "passive"))
      (node (ref "U111") (pin "5") (pinfunction "OUT_B_5") (pintype "passive"))
    )
    (net (code "80") (name "Net-(U112-OUT_A)") (class "Default")
      (node (ref "R171") (pin "2") (pinfunction "2_2") (pintype "passive"))
      (node (ref "U112") (pin "7") (pinfunction "OUT_A_7") (pintype "passive"))
    )
    (net (code "81") (name "Net-(U112-OUT_B)") (class "Default")
      (node (ref "R172") (pin "2") (pinfunction "2_2") (pintype "passive"))
      (node (ref "U112") (pin "5") (pinfunction "OUT_B_5") (pintype "passive"))
    )
    (net (code "82") (name "unconnected-(U107-NC-Pad1)") (class "Default")
      (node (ref "U107") (pin "1") (pinfunction "NC_1") (pintype "passive+no_connect"))
    )
    (net (code "83") (name "unconnected-(U107-NC-Pad8)") (class "Default")
      (node (ref "U107") (pin "8") (pinfunction "NC_8") (pintype "passive+no_connect"))
    )
    (net (code "84") (name "unconnected-(U108-NC-Pad1)") (class "Default")
      (node (ref "U108") (pin "1") (pinfunction "NC_1") (pintype "passive+no_connect"))
    )
    (net (code "85") (name "unconnected-(U108-NC-Pad8)") (class "Default")
      (node (ref "U108") (pin "8") (pinfunction "NC_8") (pintype "passive+no_connect"))
    )
    (net (code "86") (name "unconnected-(U109-NC-Pad1)") (class "Default")
      (node (ref "U109") (pin "1") (pinfunction "NC_1") (pintype "passive+no_connect"))
    )
    (net (code "87") (name "unconnected-(U109-NC-Pad8)") (class "Default")
      (node (ref "U109") (pin "8") (pinfunction "NC_8") (pintype "passive+no_connect"))
    )
    (net (code "88") (name "unconnected-(U110-NC-Pad1)") (class "Default")
      (node (ref "U110") (pin "1") (pinfunction "NC_1") (pintype "passive+no_connect"))
    )
    (net (code "89") (name "unconnected-(U110-NC-Pad8)") (class "Default")
      (node (ref "U110") (pin "8") (pinfunction "NC_8") (pintype "passive+no_connect"))
    )
    (net (code "90") (name "unconnected-(U111-NC-Pad1)") (class "Default")
      (node (ref "U111") (pin "1") (pinfunction "NC_1") (pintype "passive+no_connect"))
    )
    (net (code "91") (name "unconnected-(U111-NC-Pad8)") (class "Default")
      (node (ref "U111") (pin "8") (pinfunction "NC_8") (pintype "passive+no_connect"))
    )
    (net (code "92") (name "unconnected-(U112-NC-Pad1)") (class "Default")
      (node (ref "U112") (pin "1") (pinfunction "NC_1") (pintype "passive+no_connect"))
    )
    (net (code "93") (name "unconnected-(U112-NC-Pad8)") (class "Default")
      (node (ref "U112") (pin "8") (pinfunction "NC_8") (pintype "passive+no_connect"))
    )
  )
)
